# project.net
KiCad netlist of a schematic drawn in EAGLE
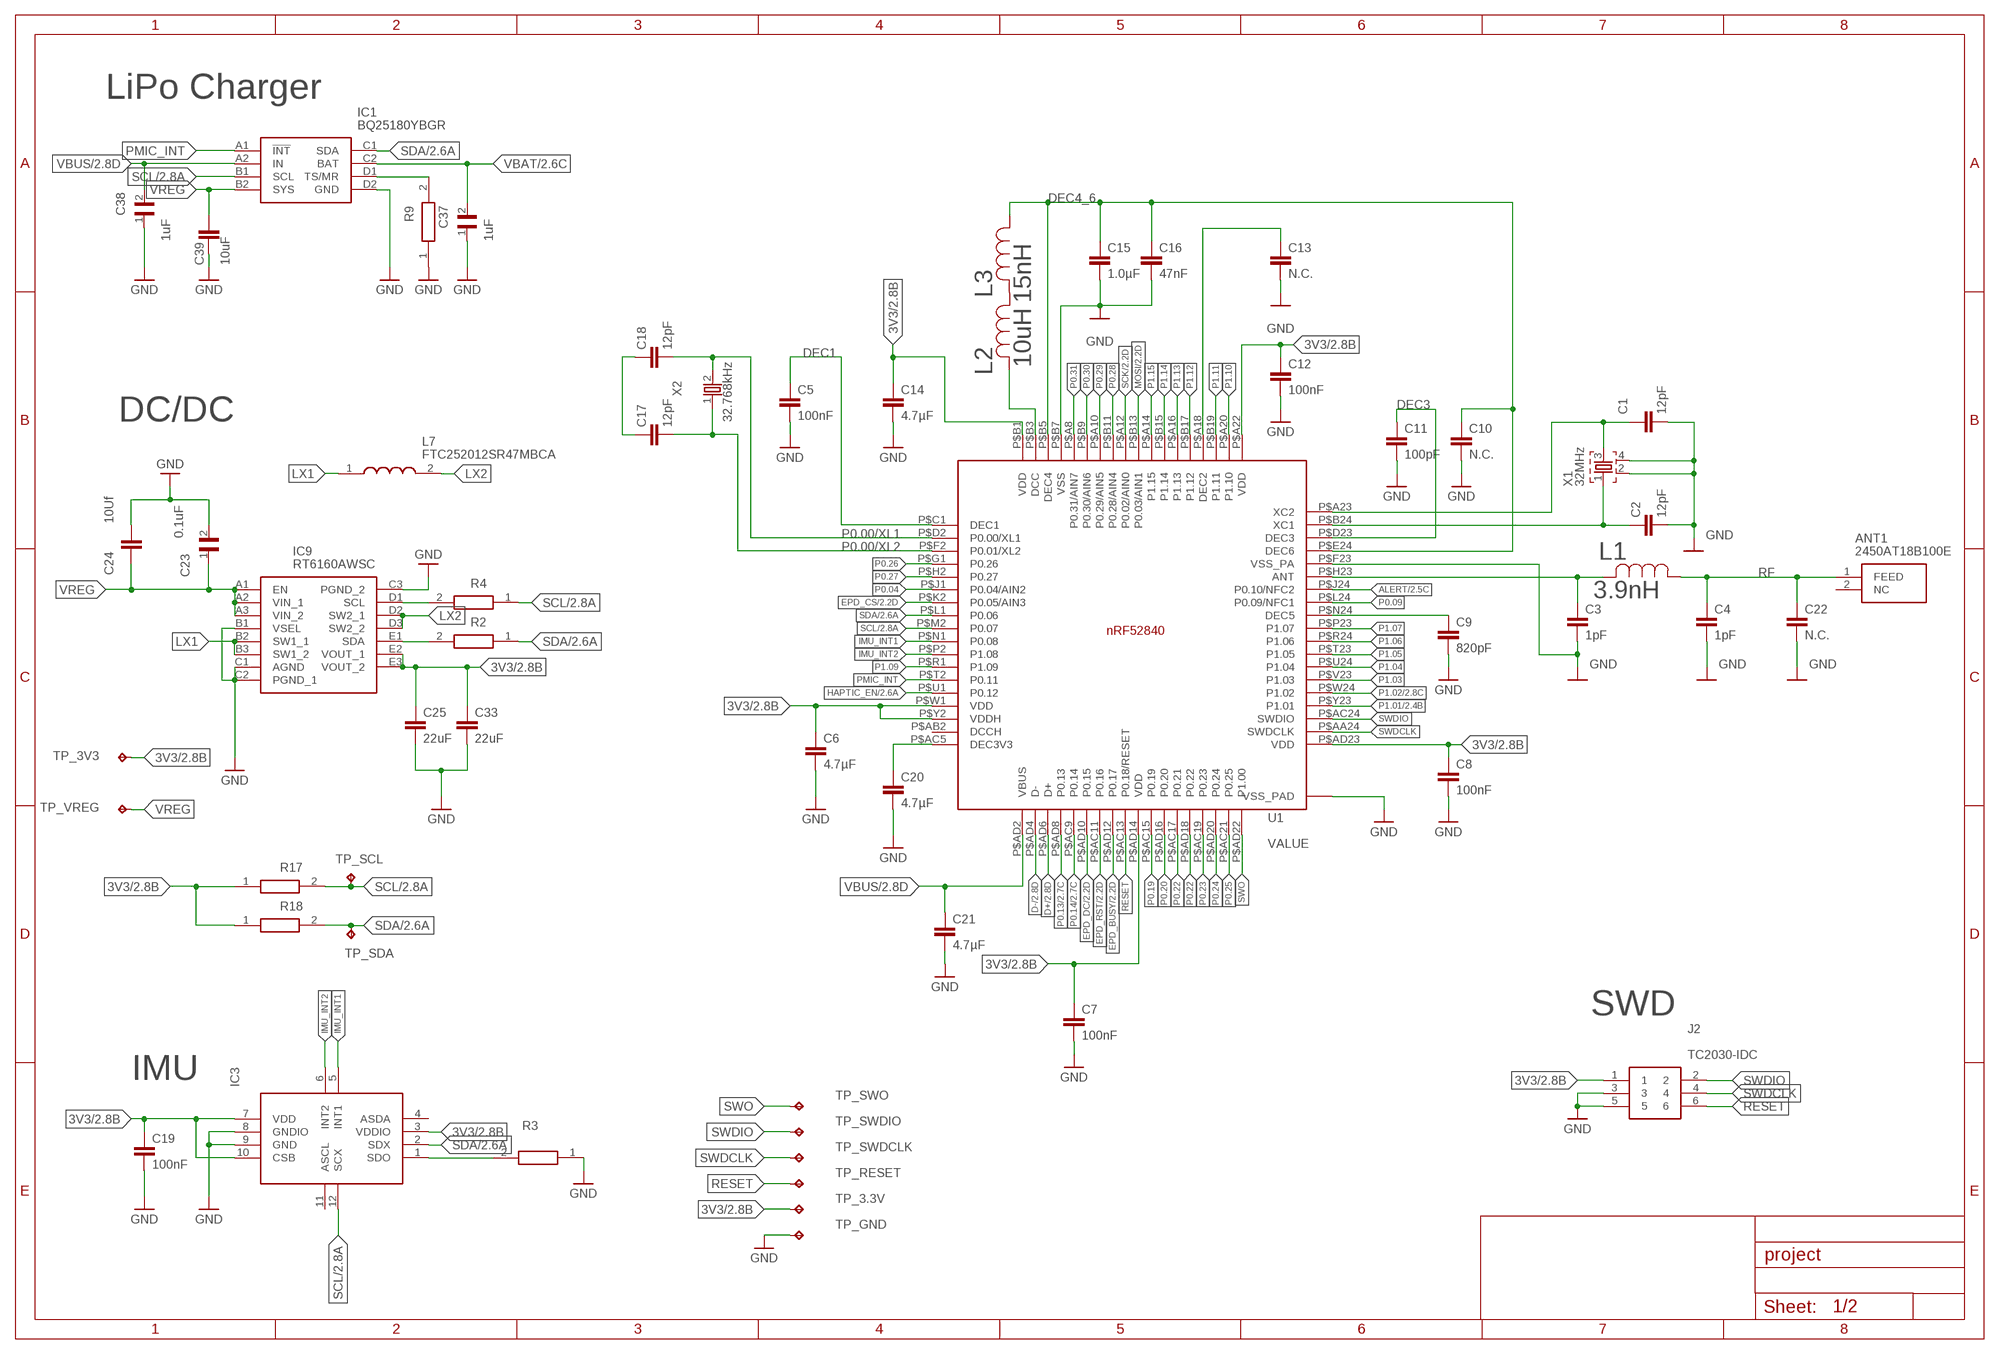
[diagram p0: schematic, sheet 1]
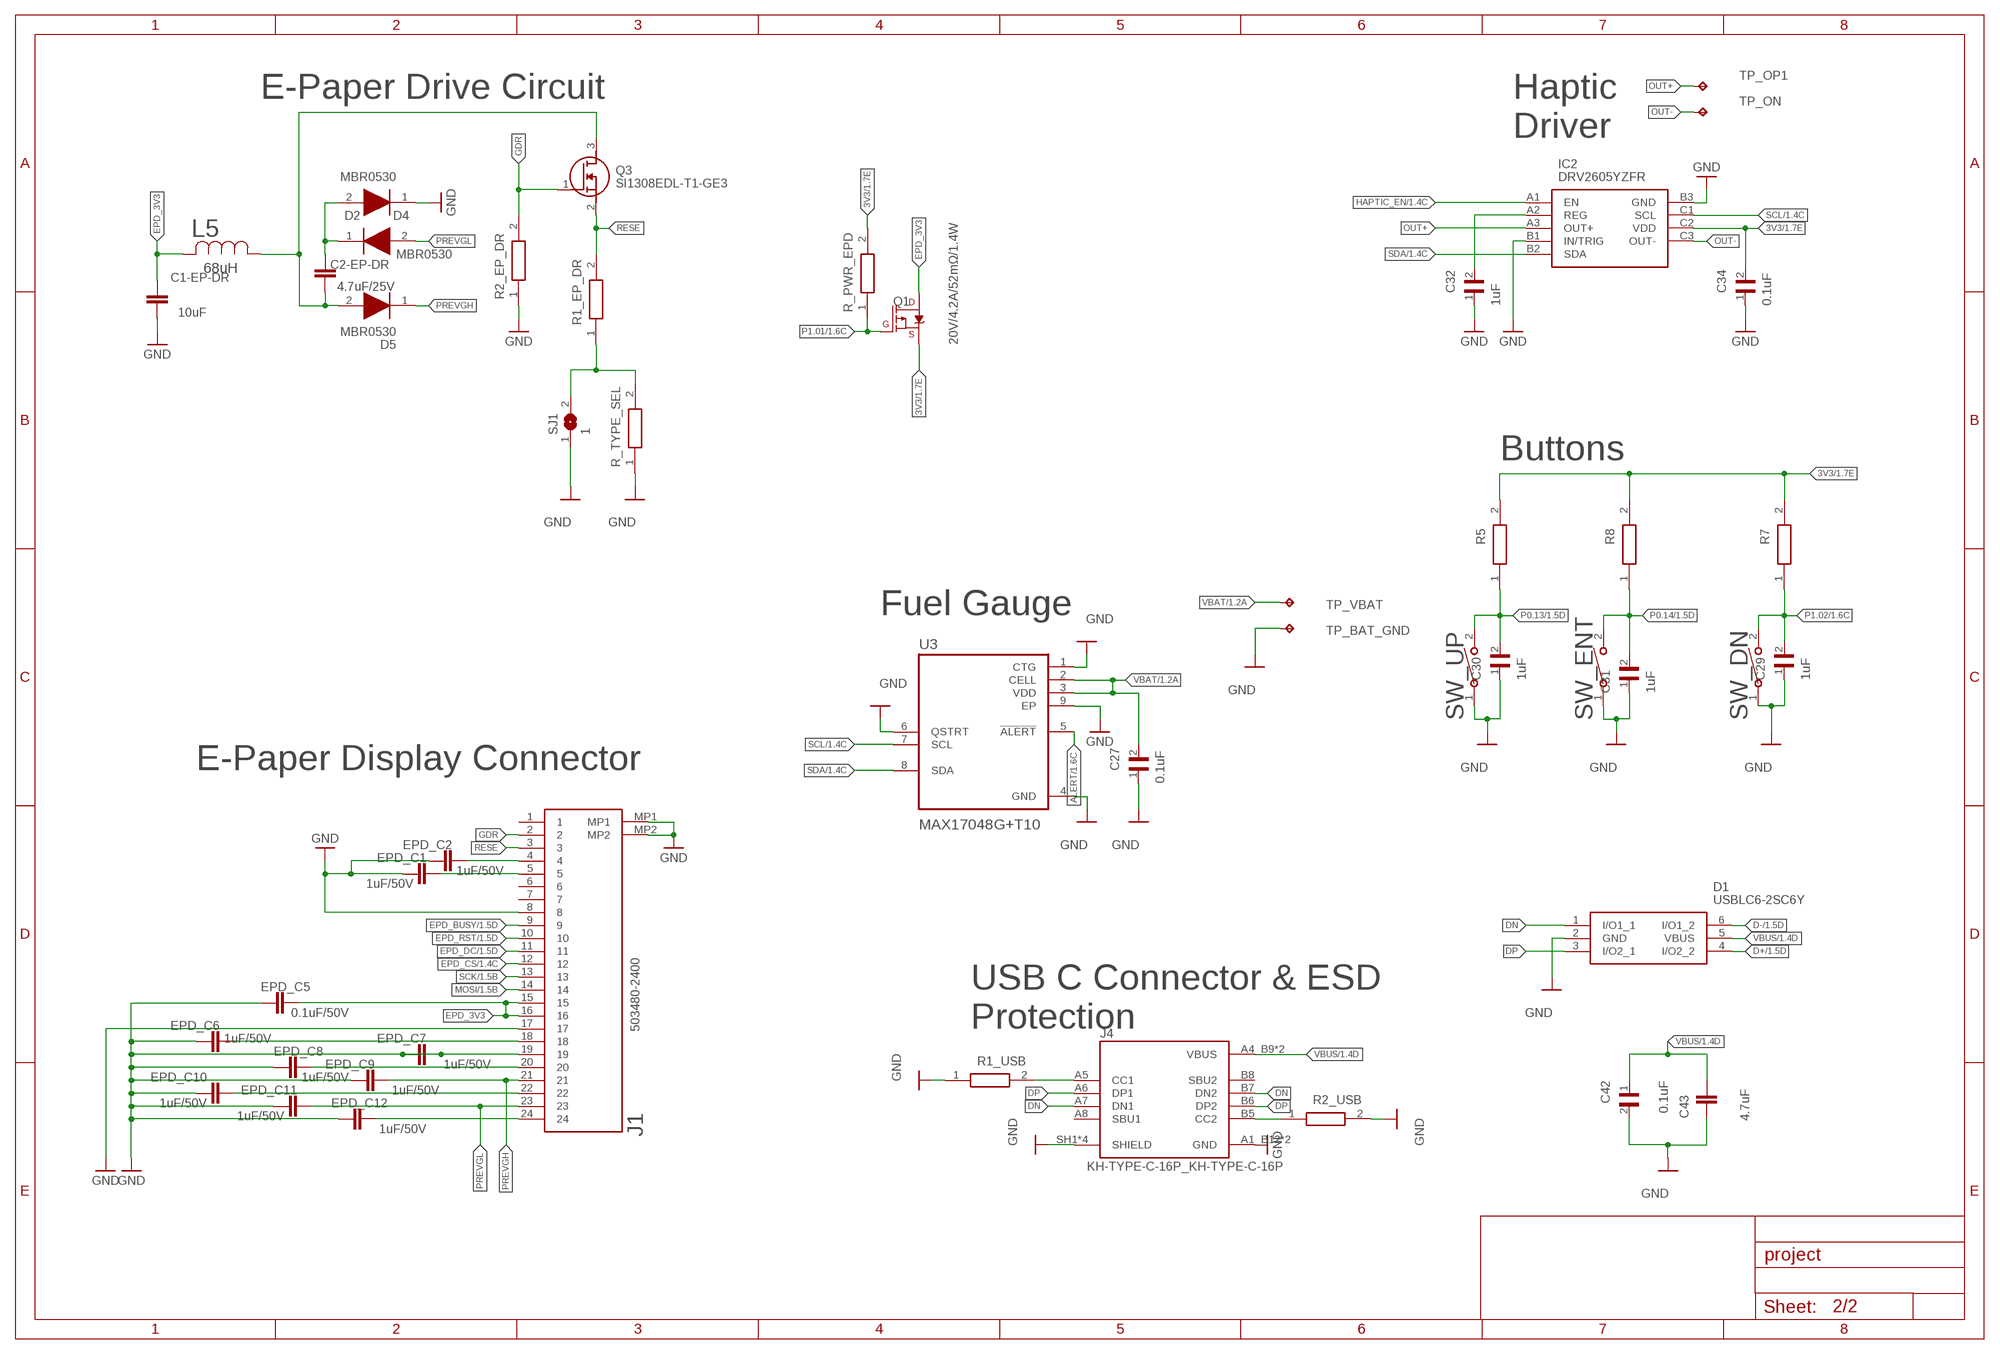
[diagram p1: schematic, sheet 2]

(export (version "E")
  (design (tool "Eeschema 10.0.6"))
  (components
    (comp (ref "C1-EP-DR")
      (value "10uF")
      (footprint "eagle-import:ESP32_C6_LIBRARY_1_ESP32_WROVER_EAGLE-LTSPICE_C0402")
      (libsource (lib "eagle-import") (part "ESP32_C6_LIBRARY_1_ESP32_WROVER_EAGLE-LTSPICE_CC0402"))
    )
    (comp (ref "C2-EP-DR")
      (value "4.7uF/25V")
      (footprint "eagle-import:ESP32_C6_LIBRARY_1_ESP32_WROVER_EAGLE-LTSPICE_C0402")
      (libsource (lib "eagle-import") (part "ESP32_C6_LIBRARY_1_ESP32_WROVER_EAGLE-LTSPICE_CC0402"))
    )
    (comp (ref "C27")
      (value "0.1uF")
      (footprint "eagle-import:GRM011R60J152KE01L_1_0201")
      (libsource (lib "eagle-import") (part "GRM011R60J152KE01L_1_GRM011R60J152KE01L"))
    )
    (comp (ref "C29")
      (value "1uF")
      (footprint "eagle-import:GRM011R60J152KE01L_1_0201")
      (libsource (lib "eagle-import") (part "GRM011R60J152KE01L_1_GRM011R60J152KE01L"))
    )
    (comp (ref "C30")
      (value "1uF")
      (footprint "eagle-import:GRM011R60J152KE01L_1_0201")
      (libsource (lib "eagle-import") (part "GRM011R60J152KE01L_1_GRM011R60J152KE01L"))
    )
    (comp (ref "C31")
      (value "1uF")
      (footprint "eagle-import:GRM011R60J152KE01L_1_0201")
      (libsource (lib "eagle-import") (part "GRM011R60J152KE01L_1_GRM011R60J152KE01L"))
    )
    (comp (ref "C32")
      (value "1uF")
      (footprint "eagle-import:GRM011R60J152KE01L_1_0201")
      (libsource (lib "eagle-import") (part "GRM011R60J152KE01L_1_GRM011R60J152KE01L"))
    )
    (comp (ref "C34")
      (value "0.1uF")
      (footprint "eagle-import:GRM011R60J152KE01L_1_0201")
      (libsource (lib "eagle-import") (part "GRM011R60J152KE01L_1_GRM011R60J152KE01L"))
    )
    (comp (ref "C42")
      (value "0.1uF")
      (footprint "eagle-import:GRM011R60J152KE01L_1_0201")
      (libsource (lib "eagle-import") (part "GRM011R60J152KE01L_1_GRM011R60J152KE01L"))
    )
    (comp (ref "C43")
      (value "4.7uF")
      (footprint "eagle-import:ESP32_C6_LIBRARY_1_ESP32_WROVER_EAGLE-LTSPICE_C0402")
      (libsource (lib "eagle-import") (part "ESP32_C6_LIBRARY_1_ESP32_WROVER_EAGLE-LTSPICE_CC0402"))
    )
    (comp (ref "D1")
      (value "USBLC6-2SC6Y")
      (footprint "eagle-import:ESP32_C6_LIBRARY_3_SOT95P280X145-6N")
      (fields (field (name "MF") "STMicroelectronics"))
      (libsource (lib "eagle-import") (part "ESP32_C6_LIBRARY_3_USBLC6-2SC6Y"))
    )
    (comp (ref "D2")
      (value "MBR0530")
      (footprint "eagle-import:ESP32_C6_LIBRARY_5_SOD3716X135N")
      (fields (field (name "MF") "ON Semiconductor"))
      (libsource (lib "eagle-import") (part "ESP32_C6_LIBRARY_5_MBR0530"))
    )
    (comp (ref "D4")
      (value "MBR0530")
      (footprint "eagle-import:ESP32_C6_LIBRARY_5_SOD3716X135N")
      (fields (field (name "MF") "ON Semiconductor"))
      (libsource (lib "eagle-import") (part "ESP32_C6_LIBRARY_5_MBR0530"))
    )
    (comp (ref "D5")
      (value "MBR0530")
      (footprint "eagle-import:ESP32_C6_LIBRARY_5_SOD3716X135N")
      (fields (field (name "MF") "ON Semiconductor"))
      (libsource (lib "eagle-import") (part "ESP32_C6_LIBRARY_5_MBR0530"))
    )
    (comp (ref "EPD_C1")
      (value "1uF/50V")
      (footprint "eagle-import:ESP32_C6_LIBRARY_1_ESP32_WROVER_EAGLE-LTSPICE_C0402")
      (libsource (lib "eagle-import") (part "ESP32_C6_LIBRARY_1_ESP32_WROVER_EAGLE-LTSPICE_CC0402"))
    )
    (comp (ref "EPD_C2")
      (value "1uF/50V")
      (footprint "eagle-import:ESP32_C6_LIBRARY_1_ESP32_WROVER_EAGLE-LTSPICE_C0402")
      (libsource (lib "eagle-import") (part "ESP32_C6_LIBRARY_1_ESP32_WROVER_EAGLE-LTSPICE_CC0402"))
    )
    (comp (ref "EPD_C5")
      (value "0.1uF/50V")
      (footprint "eagle-import:ESP32_C6_LIBRARY_1_ESP32_WROVER_EAGLE-LTSPICE_C0402")
      (libsource (lib "eagle-import") (part "ESP32_C6_LIBRARY_1_ESP32_WROVER_EAGLE-LTSPICE_CC0402"))
    )
    (comp (ref "EPD_C6")
      (value "1uF/50V")
      (footprint "eagle-import:ESP32_C6_LIBRARY_1_ESP32_WROVER_EAGLE-LTSPICE_C0402")
      (libsource (lib "eagle-import") (part "ESP32_C6_LIBRARY_1_ESP32_WROVER_EAGLE-LTSPICE_CC0402"))
    )
    (comp (ref "EPD_C7")
      (value "1uF/50V")
      (footprint "eagle-import:ESP32_C6_LIBRARY_1_ESP32_WROVER_EAGLE-LTSPICE_C0402")
      (libsource (lib "eagle-import") (part "ESP32_C6_LIBRARY_1_ESP32_WROVER_EAGLE-LTSPICE_CC0402"))
    )
    (comp (ref "EPD_C8")
      (value "1uF/50V")
      (footprint "eagle-import:ESP32_C6_LIBRARY_1_ESP32_WROVER_EAGLE-LTSPICE_C0402")
      (libsource (lib "eagle-import") (part "ESP32_C6_LIBRARY_1_ESP32_WROVER_EAGLE-LTSPICE_CC0402"))
    )
    (comp (ref "EPD_C9")
      (value "1uF/50V")
      (footprint "eagle-import:ESP32_C6_LIBRARY_1_ESP32_WROVER_EAGLE-LTSPICE_C0402")
      (libsource (lib "eagle-import") (part "ESP32_C6_LIBRARY_1_ESP32_WROVER_EAGLE-LTSPICE_CC0402"))
    )
    (comp (ref "EPD_C10")
      (value "1uF/50V")
      (footprint "eagle-import:ESP32_C6_LIBRARY_1_ESP32_WROVER_EAGLE-LTSPICE_C0402")
      (libsource (lib "eagle-import") (part "ESP32_C6_LIBRARY_1_ESP32_WROVER_EAGLE-LTSPICE_CC0402"))
    )
    (comp (ref "EPD_C11")
      (value "1uF/50V")
      (footprint "eagle-import:ESP32_C6_LIBRARY_1_ESP32_WROVER_EAGLE-LTSPICE_C0402")
      (libsource (lib "eagle-import") (part "ESP32_C6_LIBRARY_1_ESP32_WROVER_EAGLE-LTSPICE_CC0402"))
    )
    (comp (ref "EPD_C12")
      (value "1uF/50V")
      (footprint "eagle-import:ESP32_C6_LIBRARY_1_ESP32_WROVER_EAGLE-LTSPICE_C0402")
      (libsource (lib "eagle-import") (part "ESP32_C6_LIBRARY_1_ESP32_WROVER_EAGLE-LTSPICE_CC0402"))
    )
    (comp (ref "IC2")
      (value "DRV2605YZFR")
      (footprint "eagle-import:DRV2605YZFR_BGA9C50P3X3_144X144X62")
      (libsource (lib "eagle-import") (part "DRV2605YZFR_DRV2605YZFR"))
    )
    (comp (ref "J1")
      (value "503480-2400")
      (footprint "eagle-import:503480-2400_5034802400")
      (fields (field (name "MOUSER_PART_NUMBER") "538-503480-2400"))
      (libsource (lib "eagle-import") (part "503480-2400_503480-2400"))
    )
    (comp (ref "J4")
      (value "KH-TYPE-C-16P_KH-TYPE-C-16P")
      (footprint "eagle-import:KH-TYPE-C-16P_KINGHELM_KH-TYPE-C-16P")
      (fields (field (name "MF") "kinghelm") (field (name "MP") "KH-TYPE-C-16P"))
      (libsource (lib "eagle-import") (part "KH-TYPE-C-16P_KH-TYPE-C-16P"))
    )
    (comp (ref "L5")
      (value "68uH")
      (footprint "eagle-import:ESP32_C6_LIBRARY_2_IND_4828-WE-TPC_WRE")
      (fields
        (field (name "MANUFACTURER_PART_NUMBER") "744043680")
        (field (name "COPYRIGHT") "Copyright (C) 2024 Ultra Librarian. All rights reserved.")
      )
      (libsource (lib "eagle-import") (part "ESP32_C6_LIBRARY_2_744043680IND_4828-WE-TPC_WRE"))
    )
    (comp (ref "Q1")
      (value "20V/4.2A/52mΩ/1.4W")
      (footprint "eagle-import:ESP32_C6_LIBRARY_4_ESP32_C6_LIBRARY_4_ESP32_C6_LIBRARY_4_ESP32_C6_LIBRARY_4_ESP32_WROVER_SPARKFUN-DISCRETESEMI_SOT23-3")
      (libsource (lib "eagle-import") (part "ESP32_C6_LIBRARY_4_ESP32_WROVER_SPARKFUN-DISCRETESEMI_MOSFET_PCH-DMG2305UX-7"))
    )
    (comp (ref "Q3")
      (value "SI1308EDL-T1-GE3")
      (footprint "eagle-import:ESP32_C6_LIBRARY_6_SOT65P210X110-3N")
      (fields (field (name "MF") "Vishay Siliconix"))
      (libsource (lib "eagle-import") (part "ESP32_C6_LIBRARY_6_SI1308EDL-T1-GE3"))
    )
    (comp (ref "R1_EP_DR")
      (value "0.47")
      (footprint "eagle-import:ERA-1AEB3401C_0201")
      (libsource (lib "eagle-import") (part "ERA-1AEB3401C_CPF0201D7K68C1"))
    )
    (comp (ref "R1_USB")
      (value "5k1")
      (footprint "eagle-import:ERA-1AEB3401C_0201")
      (libsource (lib "eagle-import") (part "ERA-1AEB3401C_CPF0201D7K68C1"))
    )
    (comp (ref "R2_EP_DR")
      (value "10K")
      (footprint "eagle-import:ERA-1AEB3401C_0201")
      (libsource (lib "eagle-import") (part "ERA-1AEB3401C_CPF0201D7K68C1"))
    )
    (comp (ref "R2_USB")
      (value "5k1")
      (footprint "eagle-import:ERA-1AEB3401C_0201")
      (libsource (lib "eagle-import") (part "ERA-1AEB3401C_CPF0201D7K68C1"))
    )
    (comp (ref "R5")
      (value "10K")
      (footprint "eagle-import:ERA-1AEB3401C_0201")
      (libsource (lib "eagle-import") (part "ERA-1AEB3401C_CPF0201D7K68C1"))
    )
    (comp (ref "R7")
      (value "10K")
      (footprint "eagle-import:ERA-1AEB3401C_0201")
      (libsource (lib "eagle-import") (part "ERA-1AEB3401C_CPF0201D7K68C1"))
    )
    (comp (ref "R8")
      (value "10K")
      (footprint "eagle-import:ERA-1AEB3401C_0201")
      (libsource (lib "eagle-import") (part "ERA-1AEB3401C_CPF0201D7K68C1"))
    )
    (comp (ref "R_PWR_EPD")
      (value "10K")
      (footprint "eagle-import:ERA-1AEB3401C_0201")
      (libsource (lib "eagle-import") (part "ERA-1AEB3401C_CPF0201D7K68C1"))
    )
    (comp (ref "R_TYPE_SEL")
      (value "2.2")
      (footprint "eagle-import:ERA-1AEB3401C_0201")
      (libsource (lib "eagle-import") (part "ERA-1AEB3401C_CPF0201D7K68C1"))
    )
    (comp (ref "SJ1")
      (value "1")
      (footprint "eagle-import:ESP32_C6_LIBRARY_7_JUMPER_SJ")
      (libsource (lib "eagle-import") (part "ESP32_C6_LIBRARY_7_JUMPER_SJ"))
    )
    (comp (ref "SW_DN")
      (value "2025-10-22_07-23-44_LIBRARY_EVP-AKE31ASW_EVP-AKE31A_PAN")
      (footprint "eagle-import:2025-10-22_07-23-44_LIBRARY_SW_EVP-AKE31A_PAN")
      (fields
        (field (name "MANUFACTURER_PART_NUMBER") "EVP-AKE31A")
        (field (name "COPYRIGHT") "Copyright (C) 2025 Ultra Librarian. All rights reserved.")
      )
      (libsource (lib "eagle-import") (part "2025-10-22_07-23-44_LIBRARY_EVP-AKE31ASW_EVP-AKE31A_PAN"))
    )
    (comp (ref "SW_ENT")
      (value "2025-10-22_07-23-44_LIBRARY_EVP-AKE31ASW_EVP-AKE31A_PAN")
      (footprint "eagle-import:2025-10-22_07-23-44_LIBRARY_SW_EVP-AKE31A_PAN")
      (fields
        (field (name "MANUFACTURER_PART_NUMBER") "EVP-AKE31A")
        (field (name "COPYRIGHT") "Copyright (C) 2025 Ultra Librarian. All rights reserved.")
      )
      (libsource (lib "eagle-import") (part "2025-10-22_07-23-44_LIBRARY_EVP-AKE31ASW_EVP-AKE31A_PAN"))
    )
    (comp (ref "SW_UP")
      (value "SW_UP")
      (footprint "eagle-import:2025-10-22_07-23-44_LIBRARY_SW_EVP-AKE31A_PAN")
      (fields
        (field (name "MANUFACTURER_PART_NUMBER") "EVP-AKE31A")
        (field (name "COPYRIGHT") "Copyright (C) 2025 Ultra Librarian. All rights reserved.")
      )
      (libsource (lib "eagle-import") (part "2025-10-22_07-23-44_LIBRARY_EVP-AKE31ASW_EVP-AKE31A_PAN"))
    )
    (comp (ref "TP_BAT_GND")
      (value "HECTOR_WATCH_1_TPTP20R")
      (footprint "eagle-import:HECTOR_WATCH_1_TP20R")
      (libsource (lib "eagle-import") (part "HECTOR_WATCH_1_TPTP20R"))
    )
    (comp (ref "TP_ON")
      (value "HECTOR_WATCH_1_TPTP20R")
      (footprint "eagle-import:HECTOR_WATCH_1_TP20R")
      (libsource (lib "eagle-import") (part "HECTOR_WATCH_1_TPTP20R"))
    )
    (comp (ref "TP_OP1")
      (value "HECTOR_WATCH_1_TPTP20R")
      (footprint "eagle-import:HECTOR_WATCH_1_TP20R")
      (libsource (lib "eagle-import") (part "HECTOR_WATCH_1_TPTP20R"))
    )
    (comp (ref "TP_VBAT")
      (value "3V3")
      (footprint "eagle-import:HECTOR_WATCH_1_TP20R")
      (libsource (lib "eagle-import") (part "HECTOR_WATCH_1_TPTP20R"))
    )
    (comp (ref "U3")
      (value "MAX17048G+T10")
      (footprint "eagle-import:ESP32_C6_LIBRARY_SON50P200X200X80-9N")
      (fields (field (name "MF") "Analog Devices"))
      (libsource (lib "eagle-import") (part "ESP32_C6_LIBRARY_MAX17048G+T10"))
    )
    (comp (ref "ANT1")
      (value "2450AT18B100E")
      (footprint "eagle-import:2450AT18B100E_ANTC3216X140N")
      (fields (field (name "MOUSER_PART_NUMBER") "609-2450AT18B100E"))
      (libsource (lib "eagle-import") (part "2450AT18B100E_2450AT18B100E"))
    )
    (comp (ref "C1")
      (value "12pF")
      (footprint "eagle-import:PERFECT_0402_0402")
      (libsource (lib "eagle-import") (part "PERFECT_0402_CAP_0402"))
    )
    (comp (ref "C2")
      (value "12pF")
      (footprint "eagle-import:PERFECT_0402_0402")
      (libsource (lib "eagle-import") (part "PERFECT_0402_CAP_0402"))
    )
    (comp (ref "C3")
      (value "1pF")
      (footprint "eagle-import:PERFECT_0402_0402")
      (libsource (lib "eagle-import") (part "PERFECT_0402_CAP_0402"))
    )
    (comp (ref "C4")
      (value "1pF")
      (footprint "eagle-import:PERFECT_0402_0402")
      (libsource (lib "eagle-import") (part "PERFECT_0402_CAP_0402"))
    )
    (comp (ref "C5")
      (value "100nF")
      (footprint "eagle-import:PERFECT_0402_0402")
      (libsource (lib "eagle-import") (part "PERFECT_0402_CAP_0402"))
    )
    (comp (ref "C6")
      (value "4.7µF")
      (footprint "eagle-import:PERFECT_0402_0402")
      (libsource (lib "eagle-import") (part "PERFECT_0402_CAP_0402"))
    )
    (comp (ref "C7")
      (value "100nF")
      (footprint "eagle-import:PERFECT_0402_0402")
      (libsource (lib "eagle-import") (part "PERFECT_0402_CAP_0402"))
    )
    (comp (ref "C8")
      (value "100nF")
      (footprint "eagle-import:PERFECT_0402_0402")
      (libsource (lib "eagle-import") (part "PERFECT_0402_CAP_0402"))
    )
    (comp (ref "C9")
      (value "820pF")
      (footprint "eagle-import:PERFECT_0402_0402")
      (libsource (lib "eagle-import") (part "PERFECT_0402_CAP_0402"))
    )
    (comp (ref "C10")
      (value "N.C.")
      (footprint "eagle-import:PERFECT_0402_0402")
      (libsource (lib "eagle-import") (part "PERFECT_0402_CAP_0402"))
    )
    (comp (ref "C11")
      (value "100pF")
      (footprint "eagle-import:PERFECT_0402_0402")
      (libsource (lib "eagle-import") (part "PERFECT_0402_CAP_0402"))
    )
    (comp (ref "C12")
      (value "100nF")
      (footprint "eagle-import:PERFECT_0402_0402")
      (libsource (lib "eagle-import") (part "PERFECT_0402_CAP_0402"))
    )
    (comp (ref "C13")
      (value "N.C.")
      (footprint "eagle-import:PERFECT_0402_0402")
      (libsource (lib "eagle-import") (part "PERFECT_0402_CAP_0402"))
    )
    (comp (ref "C14")
      (value "4.7µF")
      (footprint "eagle-import:PERFECT_0402_0402")
      (libsource (lib "eagle-import") (part "PERFECT_0402_CAP_0402"))
    )
    (comp (ref "C15")
      (value "1.0µF")
      (footprint "eagle-import:PERFECT_0402_0402")
      (libsource (lib "eagle-import") (part "PERFECT_0402_CAP_0402"))
    )
    (comp (ref "C16")
      (value "47nF")
      (footprint "eagle-import:PERFECT_0402_0402")
      (libsource (lib "eagle-import") (part "PERFECT_0402_CAP_0402"))
    )
    (comp (ref "C17")
      (value "12pF")
      (footprint "eagle-import:PERFECT_0402_0402")
      (libsource (lib "eagle-import") (part "PERFECT_0402_CAP_0402"))
    )
    (comp (ref "C18")
      (value "12pF")
      (footprint "eagle-import:PERFECT_0402_0402")
      (libsource (lib "eagle-import") (part "PERFECT_0402_CAP_0402"))
    )
    (comp (ref "C19")
      (value "100nF")
      (footprint "eagle-import:PERFECT_0402_0402")
      (libsource (lib "eagle-import") (part "PERFECT_0402_CAP_0402"))
    )
    (comp (ref "C20")
      (value "4.7µF")
      (footprint "eagle-import:PERFECT_0402_0402")
      (libsource (lib "eagle-import") (part "PERFECT_0402_CAP_0402"))
    )
    (comp (ref "C21")
      (value "4.7µF")
      (footprint "eagle-import:PERFECT_0402_0402")
      (libsource (lib "eagle-import") (part "PERFECT_0402_CAP_0402"))
    )
    (comp (ref "C22")
      (value "N.C.")
      (footprint "eagle-import:PERFECT_0402_0402")
      (libsource (lib "eagle-import") (part "PERFECT_0402_CAP_0402"))
    )
    (comp (ref "C23")
      (value "0.1uF")
      (footprint "eagle-import:GRM011R60J152KE01L_1_0201")
      (libsource (lib "eagle-import") (part "GRM011R60J152KE01L_1_GRM011R60J152KE01L"))
    )
    (comp (ref "C24")
      (value "10Uf")
      (footprint "eagle-import:PERFECT_0402_0402")
      (libsource (lib "eagle-import") (part "PERFECT_0402_CAP_0402"))
    )
    (comp (ref "C25")
      (value "22uF")
      (footprint "eagle-import:PERFECT_0402_0402")
      (libsource (lib "eagle-import") (part "PERFECT_0402_CAP_0402"))
    )
    (comp (ref "C33")
      (value "22uF")
      (footprint "eagle-import:PERFECT_0402_0402")
      (libsource (lib "eagle-import") (part "PERFECT_0402_CAP_0402"))
    )
    (comp (ref "C37")
      (value "1uF")
      (footprint "eagle-import:GRM011R60J152KE01L_1_0201")
      (libsource (lib "eagle-import") (part "GRM011R60J152KE01L_1_GRM011R60J152KE01L"))
    )
    (comp (ref "C38")
      (value "1uF")
      (footprint "eagle-import:GRM011R60J152KE01L_1_0201")
      (libsource (lib "eagle-import") (part "GRM011R60J152KE01L_1_GRM011R60J152KE01L"))
    )
    (comp (ref "C39")
      (value "10uF")
      (footprint "eagle-import:PERFECT_0402_0402")
      (libsource (lib "eagle-import") (part "PERFECT_0402_CAP_0402"))
    )
    (comp (ref "IC1")
      (value "BQ25180YBGR")
      (footprint "eagle-import:BQ25180YBGR_BGA8C40P2X4_100X155X50")
      (fields (field (name "MOUSER_PART_NUMBER") "595-BQ25180YBGR"))
      (libsource (lib "eagle-import") (part "BQ25180YBGR_BQ25180YBGR"))
    )
    (comp (ref "IC3")
      (value "BMA421")
      (footprint "eagle-import:BMA423_BMA423")
      (fields
        (field (name "MANUFACTURER_PART_NUMBER") "BMA423")
        (field (name "MOUSER_PART_NUMBER") "262-BMA423")
      )
      (libsource (lib "eagle-import") (part "BMA423_BMA423"))
    )
    (comp (ref "IC9")
      (value "RT6160AWSC")
      (footprint "eagle-import:RT6160AWSC_BGA15C40P3X5_140X230X60")
      (fields (field (name "MOUSER_PART_NUMBER") "835-RT6160AWSC"))
      (libsource (lib "eagle-import") (part "RT6160AWSC_RT6160AWSC"))
    )
    (comp (ref "J2")
      (value "TC2030-IDC")
      (footprint "eagle-import:TC2030-IDC_TC2030IDC")
      (libsource (lib "eagle-import") (part "TC2030-IDC_TC2030-IDC"))
    )
    (comp (ref "L1")
      (value "3.9nH")
      (footprint "eagle-import:ESP32_C6_LIBRARY_2_IND_4828-WE-TPC_WRE")
      (fields
        (field (name "MANUFACTURER_PART_NUMBER") "744043680")
        (field (name "COPYRIGHT") "Copyright (C) 2024 Ultra Librarian. All rights reserved.")
      )
      (libsource (lib "eagle-import") (part "ESP32_C6_LIBRARY_2_744043680IND_4828-WE-TPC_WRE"))
    )
    (comp (ref "L2")
      (value "10uH")
      (footprint "eagle-import:ESP32_C6_LIBRARY_2_IND_4828-WE-TPC_WRE")
      (fields
        (field (name "MANUFACTURER_PART_NUMBER") "744043680")
        (field (name "COPYRIGHT") "Copyright (C) 2024 Ultra Librarian. All rights reserved.")
      )
      (libsource (lib "eagle-import") (part "ESP32_C6_LIBRARY_2_744043680IND_4828-WE-TPC_WRE"))
    )
    (comp (ref "L3")
      (value "15nH")
      (footprint "eagle-import:ESP32_C6_LIBRARY_2_IND_4828-WE-TPC_WRE")
      (fields
        (field (name "MANUFACTURER_PART_NUMBER") "744043680")
        (field (name "COPYRIGHT") "Copyright (C) 2024 Ultra Librarian. All rights reserved.")
      )
      (libsource (lib "eagle-import") (part "ESP32_C6_LIBRARY_2_744043680IND_4828-WE-TPC_WRE"))
    )
    (comp (ref "L7")
      (value "FTC252012SR47MBCA")
      (footprint "eagle-import:MLP2016SR47MT0S1_INDC2016X100N")
      (libsource (lib "eagle-import") (part "MLP2016SR47MT0S1_FTC252012SR47MBCA"))
    )
    (comp (ref "R2")
      (value "0")
      (footprint "eagle-import:ERA-1AEB3401C_0201")
      (libsource (lib "eagle-import") (part "ERA-1AEB3401C_CPF0201D7K68C1"))
    )
    (comp (ref "R3")
      (value "ERA-1AEB3401C_CPF0201D7K68C1")
      (footprint "eagle-import:ERA-1AEB3401C_0201")
      (libsource (lib "eagle-import") (part "ERA-1AEB3401C_CPF0201D7K68C1"))
    )
    (comp (ref "R4")
      (value "0")
      (footprint "eagle-import:ERA-1AEB3401C_0201")
      (libsource (lib "eagle-import") (part "ERA-1AEB3401C_CPF0201D7K68C1"))
    )
    (comp (ref "R9")
      (value "10K")
      (footprint "eagle-import:ERA-1AEB3401C_0201")
      (libsource (lib "eagle-import") (part "ERA-1AEB3401C_CPF0201D7K68C1"))
    )
    (comp (ref "R17")
      (value "3K3")
      (footprint "eagle-import:ERA-1AEB3401C_0201")
      (libsource (lib "eagle-import") (part "ERA-1AEB3401C_CPF0201D7K68C1"))
    )
    (comp (ref "R18")
      (value "3K3")
      (footprint "eagle-import:ERA-1AEB3401C_0201")
      (libsource (lib "eagle-import") (part "ERA-1AEB3401C_CPF0201D7K68C1"))
    )
    (comp (ref "TP_3.3V")
      (value "HECTOR_WATCH_1_TPTP20R")
      (footprint "eagle-import:HECTOR_WATCH_1_TP20R")
      (libsource (lib "eagle-import") (part "HECTOR_WATCH_1_TPTP20R"))
    )
    (comp (ref "TP_3V3")
      (value "HECTOR_WATCH_1_TPTP20R")
      (footprint "eagle-import:HECTOR_WATCH_1_TP20R")
      (libsource (lib "eagle-import") (part "HECTOR_WATCH_1_TPTP20R"))
    )
    (comp (ref "TP_GND")
      (value "HECTOR_WATCH_1_TPTP20R")
      (footprint "eagle-import:HECTOR_WATCH_1_TP20R")
      (libsource (lib "eagle-import") (part "HECTOR_WATCH_1_TPTP20R"))
    )
    (comp (ref "TP_RESET")
      (value "HECTOR_WATCH_1_TPTP20R")
      (footprint "eagle-import:HECTOR_WATCH_1_TP20R")
      (libsource (lib "eagle-import") (part "HECTOR_WATCH_1_TPTP20R"))
    )
    (comp (ref "TP_SCL")
      (value "HECTOR_WATCH_1_TPTP20R")
      (footprint "eagle-import:HECTOR_WATCH_1_TP20R")
      (libsource (lib "eagle-import") (part "HECTOR_WATCH_1_TPTP20R"))
    )
    (comp (ref "TP_SDA")
      (value "HECTOR_WATCH_1_TPTP20R")
      (footprint "eagle-import:HECTOR_WATCH_1_TP20R")
      (libsource (lib "eagle-import") (part "HECTOR_WATCH_1_TPTP20R"))
    )
    (comp (ref "TP_SWDCLK")
      (value "HECTOR_WATCH_1_TPTP20R")
      (footprint "eagle-import:HECTOR_WATCH_1_TP20R")
      (libsource (lib "eagle-import") (part "HECTOR_WATCH_1_TPTP20R"))
    )
    (comp (ref "TP_SWDIO")
      (value "HECTOR_WATCH_1_TPTP20R")
      (footprint "eagle-import:HECTOR_WATCH_1_TP20R")
      (libsource (lib "eagle-import") (part "HECTOR_WATCH_1_TPTP20R"))
    )
    (comp (ref "TP_SWO")
      (value "HECTOR_WATCH_1_TPTP20R")
      (footprint "eagle-import:HECTOR_WATCH_1_TP20R")
      (libsource (lib "eagle-import") (part "HECTOR_WATCH_1_TPTP20R"))
    )
    (comp (ref "TP_VREG")
      (value "HECTOR_WATCH_1_TPTP20R")
      (footprint "eagle-import:HECTOR_WATCH_1_TP20R")
      (libsource (lib "eagle-import") (part "HECTOR_WATCH_1_TPTP20R"))
    )
    (comp (ref "U1")
      (value "NRF52840_QF")
      (footprint "eagle-import:NORDIC_NRF_4_AQFN50P700X700X85_HS-74N")
      (libsource (lib "eagle-import") (part "NORDIC_NRF_4_NRF52840_QF"))
    )
    (comp (ref "X1")
      (value "32MHz")
      (footprint "eagle-import:NORDIC_NRF_BT-XTAL_2016_N")
      (libsource (lib "eagle-import") (part "NORDIC_NRF_XTAL_32MHZ"))
    )
    (comp (ref "X2")
      (value "32.768kHz")
      (footprint "eagle-import:NORDIC_NRF_1_XTAL_3215_N")
      (libsource (lib "eagle-import") (part "NORDIC_NRF_1_XTAL_32KHZ"))
    )
  )
  (nets
    (net (code "1") (name "3V3") (class "Default")
      (node (ref "C12") (pin "1") (pinfunction "1_1") (pintype "passive"))
      (node (ref "C14") (pin "1") (pinfunction "1_1") (pintype "passive"))
      (node (ref "C19") (pin "1") (pinfunction "1_1") (pintype "passive"))
      (node (ref "C25") (pin "1") (pinfunction "1_1") (pintype "passive"))
      (node (ref "C33") (pin "1") (pinfunction "1_1") (pintype "passive"))
      (node (ref "C34") (pin "2") (pinfunction "2_2") (pintype "passive"))
      (node (ref "C6") (pin "1") (pinfunction "1_1") (pintype "passive"))
      (node (ref "C7") (pin "1") (pinfunction "1_1") (pintype "passive"))
      (node (ref "C8") (pin "1") (pinfunction "1_1") (pintype "passive"))
      (node (ref "IC2") (pin "C2") (pinfunction "VDD_C2") (pintype "bidirectional"))
      (node (ref "IC3") (pin "10") (pinfunction "CSB_10") (pintype "bidirectional"))
      (node (ref "IC3") (pin "3") (pinfunction "VDDIO_3") (pintype "bidirectional"))
      (node (ref "IC3") (pin "7") (pinfunction "VDD_7") (pintype "bidirectional"))
      (node (ref "IC9") (pin "E2") (pinfunction "VOUT_1_E2") (pintype "bidirectional"))
      (node (ref "IC9") (pin "E3") (pinfunction "VOUT_2_E3") (pintype "bidirectional"))
      (node (ref "J2") (pin "1") (pinfunction "1_1") (pintype "bidirectional"))
      (node (ref "Q1") (pin "2") (pinfunction "S_2") (pintype "bidirectional"))
      (node (ref "R17") (pin "1") (pinfunction "1_1") (pintype "bidirectional"))
      (node (ref "R18") (pin "1") (pinfunction "1_1") (pintype "bidirectional"))
      (node (ref "R5") (pin "2") (pinfunction "2_2") (pintype "bidirectional"))
      (node (ref "R7") (pin "2") (pinfunction "2_2") (pintype "bidirectional"))
      (node (ref "R8") (pin "2") (pinfunction "2_2") (pintype "bidirectional"))
      (node (ref "R_PWR_EPD") (pin "2") (pinfunction "2_2") (pintype "bidirectional"))
      (node (ref "TP_3.3V") (pin "TP") (pinfunction "TP_TP") (pintype "input"))
      (node (ref "TP_3V3") (pin "TP") (pinfunction "TP_TP") (pintype "input"))
      (node (ref "U1") (pin "P$A22") (pinfunction "VDD_P$A22") (pintype "power_in"))
      (node (ref "U1") (pin "P$AD14") (pinfunction "VDD_P$AD14") (pintype "power_in"))
      (node (ref "U1") (pin "P$AD23") (pinfunction "VDD_P$AD23") (pintype "power_in"))
      (node (ref "U1") (pin "P$B1") (pinfunction "VDD_P$B1") (pintype "power_in"))
      (node (ref "U1") (pin "P$W1") (pinfunction "VDD_P$W1") (pintype "power_in"))
      (node (ref "U1") (pin "P$Y2") (pinfunction "VDDH_P$Y2") (pintype "power_in"))
    )
    (net (code "2") (name "ALERT") (class "Default")
      (node (ref "U1") (pin "P$J24") (pinfunction "P0.10/NFC2_P$J24") (pintype "bidirectional"))
      (node (ref "U3") (pin "5") (pinfunction "~{ALERT}_5") (pintype "output"))
    )
    (net (code "3") (name "D+") (class "Default")
      (node (ref "D1") (pin "4") (pinfunction "I/O2_2_4") (pintype "bidirectional"))
      (node (ref "U1") (pin "P$AD6") (pinfunction "D+_P$AD6") (pintype "bidirectional"))
    )
    (net (code "4") (name "D-") (class "Default")
      (node (ref "D1") (pin "6") (pinfunction "I/O1_2_6") (pintype "bidirectional"))
      (node (ref "U1") (pin "P$AD4") (pinfunction "D-_P$AD4") (pintype "bidirectional"))
    )
    (net (code "5") (name "DEC1") (class "Default")
      (node (ref "C5") (pin "1") (pinfunction "1_1") (pintype "passive"))
      (node (ref "U1") (pin "P$C1") (pinfunction "DEC1_P$C1") (pintype "power_in"))
    )
    (net (code "6") (name "DEC3") (class "Default")
      (node (ref "C11") (pin "1") (pinfunction "1_1") (pintype "passive"))
      (node (ref "U1") (pin "P$D23") (pinfunction "DEC3_P$D23") (pintype "bidirectional"))
    )
    (net (code "7") (name "DEC4_6") (class "Default")
      (node (ref "C10") (pin "1") (pinfunction "1_1") (pintype "passive"))
      (node (ref "C15") (pin "1") (pinfunction "1_1") (pintype "passive"))
      (node (ref "C16") (pin "1") (pinfunction "1_1") (pintype "passive"))
      (node (ref "L3") (pin "1") (pinfunction "1_1") (pintype "passive"))
      (node (ref "U1") (pin "P$B5") (pinfunction "DEC4_P$B5") (pintype "power_in"))
      (node (ref "U1") (pin "P$E24") (pinfunction "DEC6_P$E24") (pintype "bidirectional"))
    )
    (net (code "8") (name "DN") (class "Default")
      (node (ref "D1") (pin "1") (pinfunction "I/O1_1_1") (pintype "bidirectional"))
      (node (ref "J4") (pin "A7") (pinfunction "DN1_A7") (pintype "bidirectional"))
      (node (ref "J4") (pin "B7") (pinfunction "DN2_B7") (pintype "bidirectional"))
    )
    (net (code "9") (name "DP") (class "Default")
      (node (ref "D1") (pin "3") (pinfunction "I/O2_1_3") (pintype "bidirectional"))
      (node (ref "J4") (pin "A6") (pinfunction "DP1_A6") (pintype "bidirectional"))
      (node (ref "J4") (pin "B6") (pinfunction "DP2_B6") (pintype "bidirectional"))
    )
    (net (code "10") (name "EPD_3V3") (class "Default")
      (node (ref "C1-EP-DR") (pin "2") (pinfunction "2_2") (pintype "passive"))
      (node (ref "EPD_C5") (pin "2") (pinfunction "2_2") (pintype "passive"))
      (node (ref "J1") (pin "15") (pinfunction "15_15") (pintype "bidirectional"))
      (node (ref "J1") (pin "16") (pinfunction "16_16") (pintype "bidirectional"))
      (node (ref "L5") (pin "2") (pinfunction "2_2") (pintype "passive"))
      (node (ref "Q1") (pin "3") (pinfunction "D_3") (pintype "bidirectional"))
    )
    (net (code "11") (name "EPD_BUSY") (class "Default")
      (node (ref "J1") (pin "9") (pinfunction "9_9") (pintype "bidirectional"))
      (node (ref "U1") (pin "P$AD12") (pinfunction "P0.17_P$AD12") (pintype "bidirectional"))
    )
    (net (code "12") (name "EPD_CS") (class "Default")
      (node (ref "J1") (pin "12") (pinfunction "12_12") (pintype "bidirectional"))
      (node (ref "U1") (pin "P$K2") (pinfunction "P0.05/AIN3_P$K2") (pintype "bidirectional"))
    )
    (net (code "13") (name "EPD_DC") (class "Default")
      (node (ref "J1") (pin "11") (pinfunction "11_11") (pintype "bidirectional"))
      (node (ref "U1") (pin "P$AD10") (pinfunction "P0.15_P$AD10") (pintype "bidirectional"))
    )
    (net (code "14") (name "EPD_RST") (class "Default")
      (node (ref "J1") (pin "10") (pinfunction "10_10") (pintype "bidirectional"))
      (node (ref "U1") (pin "P$AC11") (pinfunction "P0.16_P$AC11") (pintype "bidirectional"))
    )
    (net (code "15") (name "GDR") (class "Default")
      (node (ref "J1") (pin "2") (pinfunction "2_2") (pintype "bidirectional"))
      (node (ref "Q3") (pin "1") (pinfunction "G_1") (pintype "bidirectional"))
      (node (ref "R2_EP_DR") (pin "2") (pinfunction "2_2") (pintype "bidirectional"))
    )
    (net (code "16") (name "GND") (class "Default")
      (node (ref "C1") (pin "2") (pinfunction "2_2") (pintype "passive"))
      (node (ref "C1-EP-DR") (pin "1") (pinfunction "1_1") (pintype "passive"))
      (node (ref "C10") (pin "2") (pinfunction "2_2") (pintype "passive"))
      (node (ref "C11") (pin "2") (pinfunction "2_2") (pintype "passive"))
      (node (ref "C12") (pin "2") (pinfunction "2_2") (pintype "passive"))
      (node (ref "C13") (pin "2") (pinfunction "2_2") (pintype "passive"))
      (node (ref "C14") (pin "2") (pinfunction "2_2") (pintype "passive"))
      (node (ref "C15") (pin "2") (pinfunction "2_2") (pintype "passive"))
      (node (ref "C16") (pin "2") (pinfunction "2_2") (pintype "passive"))
      (node (ref "C19") (pin "2") (pinfunction "2_2") (pintype "passive"))
      (node (ref "C2") (pin "2") (pinfunction "2_2") (pintype "passive"))
      (node (ref "C20") (pin "2") (pinfunction "2_2") (pintype "passive"))
      (node (ref "C21") (pin "2") (pinfunction "2_2") (pintype "passive"))
      (node (ref "C22") (pin "2") (pinfunction "2_2") (pintype "passive"))
      (node (ref "C23") (pin "2") (pinfunction "2_2") (pintype "passive"))
      (node (ref "C24") (pin "1") (pinfunction "1_1") (pintype "passive"))
      (node (ref "C25") (pin "2") (pinfunction "2_2") (pintype "passive"))
      (node (ref "C27") (pin "1") (pinfunction "1_1") (pintype "passive"))
      (node (ref "C29") (pin "1") (pinfunction "1_1") (pintype "passive"))
      (node (ref "C3") (pin "2") (pinfunction "2_2") (pintype "passive"))
      (node (ref "C30") (pin "1") (pinfunction "1_1") (pintype "passive"))
      (node (ref "C31") (pin "1") (pinfunction "1_1") (pintype "passive"))
      (node (ref "C32") (pin "1") (pinfunction "1_1") (pintype "passive"))
      (node (ref "C33") (pin "2") (pinfunction "2_2") (pintype "passive"))
      (node (ref "C34") (pin "1") (pinfunction "1_1") (pintype "passive"))
      (node (ref "C37") (pin "1") (pinfunction "1_1") (pintype "passive"))
      (node (ref "C38") (pin "1") (pinfunction "1_1") (pintype "passive"))
      (node (ref "C39") (pin "2") (pinfunction "2_2") (pintype "passive"))
      (node (ref "C4") (pin "2") (pinfunction "2_2") (pintype "passive"))
      (node (ref "C42") (pin "2") (pinfunction "2_2") (pintype "passive"))
      (node (ref "C43") (pin "1") (pinfunction "1_1") (pintype "passive"))
      (node (ref "C5") (pin "2") (pinfunction "2_2") (pintype "passive"))
      (node (ref "C6") (pin "2") (pinfunction "2_2") (pintype "passive"))
      (node (ref "C7") (pin "2") (pinfunction "2_2") (pintype "passive"))
      (node (ref "C8") (pin "2") (pinfunction "2_2") (pintype "passive"))
      (node (ref "C9") (pin "2") (pinfunction "2_2") (pintype "passive"))
      (node (ref "D1") (pin "2") (pinfunction "GND_2") (pintype "bidirectional"))
      (node (ref "D4") (pin "1") (pinfunction "K_1") (pintype "bidirectional"))
      (node (ref "EPD_C1") (pin "1") (pinfunction "1_1") (pintype "passive"))
      (node (ref "EPD_C10") (pin "1") (pinfunction "1_1") (pintype "passive"))
      (node (ref "EPD_C11") (pin "1") (pinfunction "1_1") (pintype "passive"))
      (node (ref "EPD_C12") (pin "1") (pinfunction "1_1") (pintype "passive"))
      (node (ref "EPD_C2") (pin "1") (pinfunction "1_1") (pintype "passive"))
      (node (ref "EPD_C5") (pin "1") (pinfunction "1_1") (pintype "passive"))
      (node (ref "EPD_C6") (pin "1") (pinfunction "1_1") (pintype "passive"))
      (node (ref "EPD_C7") (pin "1") (pinfunction "1_1") (pintype "passive"))
      (node (ref "EPD_C7") (pin "2") (pinfunction "2_2") (pintype "passive"))
      (node (ref "EPD_C8") (pin "1") (pinfunction "1_1") (pintype "passive"))
      (node (ref "EPD_C9") (pin "1") (pinfunction "1_1") (pintype "passive"))
      (node (ref "IC1") (pin "D2") (pinfunction "GND_D2") (pintype "bidirectional"))
      (node (ref "IC2") (pin "B1") (pinfunction "IN/TRIG_B1") (pintype "bidirectional"))
      (node (ref "IC2") (pin "B3") (pinfunction "GND_B3") (pintype "bidirectional"))
      (node (ref "IC3") (pin "8") (pinfunction "GNDIO_8") (pintype "bidirectional"))
      (node (ref "IC3") (pin "9") (pinfunction "GND_9") (pintype "bidirectional"))
      (node (ref "IC9") (pin "B1") (pinfunction "VSEL_B1") (pintype "bidirectional"))
      (node (ref "IC9") (pin "C1") (pinfunction "AGND_C1") (pintype "bidirectional"))
      (node (ref "IC9") (pin "C2") (pinfunction "PGND_1_C2") (pintype "bidirectional"))
      (node (ref "IC9") (pin "C3") (pinfunction "PGND_2_C3") (pintype "bidirectional"))
      (node (ref "J1") (pin "17") (pinfunction "17_17") (pintype "bidirectional"))
      (node (ref "J1") (pin "19") (pinfunction "19_19") (pintype "bidirectional"))
      (node (ref "J1") (pin "8") (pinfunction "8_8") (pintype "bidirectional"))
      (node (ref "J1") (pin "MP1") (pinfunction "MP1_MP1") (pintype "bidirectional"))
      (node (ref "J1") (pin "MP2") (pinfunction "MP2_MP2") (pintype "bidirectional"))
      (node (ref "J2") (pin "3") (pinfunction "3_3") (pintype "bidirectional"))
      (node (ref "J2") (pin "5") (pinfunction "5_5") (pintype "bidirectional"))
      (node (ref "J4") (pin "A12_B1") (pinfunction "GND_A12_B1") (pintype "power_in"))
      (node (ref "J4") (pin "A1_B12") (pinfunction "GND_A1_B12") (pintype "power_in"))
      (node (ref "J4") (pin "SH1") (pinfunction "SHIELD_SH1") (pintype "passive"))
      (node (ref "J4") (pin "SH2") (pinfunction "SHIELD_SH2") (pintype "passive"))
      (node (ref "J4") (pin "SH3") (pinfunction "SHIELD_SH3") (pintype "passive"))
      (node (ref "J4") (pin "SH4") (pinfunction "SHIELD_SH4") (pintype "passive"))
      (node (ref "R1_USB") (pin "1") (pinfunction "1_1") (pintype "bidirectional"))
      (node (ref "R2_EP_DR") (pin "1") (pinfunction "1_1") (pintype "bidirectional"))
      (node (ref "R2_USB") (pin "2") (pinfunction "2_2") (pintype "bidirectional"))
      (node (ref "R3") (pin "1") (pinfunction "1_1") (pintype "bidirectional"))
      (node (ref "R9") (pin "1") (pinfunction "1_1") (pintype "bidirectional"))
      (node (ref "R_TYPE_SEL") (pin "1") (pinfunction "1_1") (pintype "bidirectional"))
      (node (ref "SJ1") (pin "1") (pinfunction "1_1") (pintype "passive"))
      (node (ref "SW_DN") (pin "1") (pinfunction "1_1") (pintype "passive"))
      (node (ref "SW_ENT") (pin "1") (pinfunction "1_1") (pintype "passive"))
      (node (ref "SW_UP") (pin "1") (pinfunction "1_1") (pintype "passive"))
      (node (ref "TP_BAT_GND") (pin "TP") (pinfunction "TP_TP") (pintype "input"))
      (node (ref "TP_GND") (pin "TP") (pinfunction "TP_TP") (pintype "input"))
      (node (ref "U1") (pin "P$74") (pinfunction "VSS_PAD_P$74") (pintype "bidirectional"))
      (node (ref "U1") (pin "P$75") (pinfunction "VSS_PAD_P$75") (pintype "bidirectional"))
      (node (ref "U1") (pin "P$76") (pinfunction "VSS_PAD_P$76") (pintype "bidirectional"))
      (node (ref "U1") (pin "P$77") (pinfunction "VSS_PAD_P$77") (pintype "bidirectional"))
      (node (ref "U1") (pin "P$78") (pinfunction "VSS_PAD_P$78") (pintype "bidirectional"))
      (node (ref "U1") (pin "P$79") (pinfunction "VSS_PAD_P$79") (pintype "bidirectional"))
      (node (ref "U1") (pin "P$80") (pinfunction "VSS_PAD_P$80") (pintype "bidirectional"))
      (node (ref "U1") (pin "P$81") (pinfunction "VSS_PAD_P$81") (pintype "bidirectional"))
      (node (ref "U1") (pin "P$82") (pinfunction "VSS_PAD_P$82") (pintype "bidirectional"))
      (node (ref "U1") (pin "P$83") (pinfunction "VSS_PAD_P$83") (pintype "bidirectional"))
      (node (ref "U1") (pin "P$84") (pinfunction "VSS_PAD_P$84") (pintype "bidirectional"))
      (node (ref "U1") (pin "P$85") (pinfunction "VSS_PAD_P$85") (pintype "bidirectional"))
      (node (ref "U1") (pin "P$86") (pinfunction "VSS_PAD_P$86") (pintype "bidirectional"))
      (node (ref "U1") (pin "P$87") (pinfunction "VSS_PAD_P$87") (pintype "bidirectional"))
      (node (ref "U1") (pin "P$88") (pinfunction "VSS_PAD_P$88") (pintype "bidirectional"))
      (node (ref "U1") (pin "P$89") (pinfunction "VSS_PAD_P$89") (pintype "bidirectional"))
      (node (ref "U1") (pin "P$90") (pinfunction "VSS_PAD_P$90") (pintype "bidirectional"))
      (node (ref "U1") (pin "P$B7") (pinfunction "VSS_P$B7") (pintype "power_in"))
      (node (ref "U1") (pin "P$F23") (pinfunction "VSS_PA_P$F23") (pintype "bidirectional"))
      (node (ref "U3") (pin "1") (pinfunction "CTG_1") (pintype "power_in"))
      (node (ref "U3") (pin "4") (pinfunction "GND_4") (pintype "power_in"))
      (node (ref "U3") (pin "6") (pinfunction "QSTRT_6") (pintype "input"))
      (node (ref "U3") (pin "9") (pinfunction "EP_9") (pintype "power_in"))
      (node (ref "X1") (pin "2") (pinfunction "2_2") (pintype "passive"))
      (node (ref "X1") (pin "4") (pinfunction "4_4") (pintype "passive"))
    )
    (net (code "17") (name "HAPTIC_EN") (class "Default")
      (node (ref "IC2") (pin "A1") (pinfunction "EN_A1") (pintype "bidirectional"))
      (node (ref "U1") (pin "P$U1") (pinfunction "P0.12_P$U1") (pintype "bidirectional"))
    )
    (net (code "18") (name "IMU_INT1") (class "Default")
      (node (ref "IC3") (pin "5") (pinfunction "INT1_5") (pintype "bidirectional"))
      (node (ref "U1") (pin "P$N1") (pinfunction "P0.08_P$N1") (pintype "bidirectional"))
    )
    (net (code "19") (name "IMU_INT2") (class "Default")
      (node (ref "IC3") (pin "6") (pinfunction "INT2_6") (pintype "bidirectional"))
      (node (ref "U1") (pin "P$P2") (pinfunction "P1.08_P$P2") (pintype "bidirectional"))
    )
    (net (code "20") (name "LX1") (class "Default")
      (node (ref "IC9") (pin "B2") (pinfunction "SW1_1_B2") (pintype "bidirectional"))
      (node (ref "IC9") (pin "B3") (pinfunction "SW1_2_B3") (pintype "bidirectional"))
      (node (ref "L7") (pin "1") (pinfunction "1_1") (pintype "bidirectional"))
    )
    (net (code "21") (name "LX2") (class "Default")
      (node (ref "IC9") (pin "D2") (pinfunction "SW2_1_D2") (pintype "bidirectional"))
      (node (ref "IC9") (pin "D3") (pinfunction "SW2_2_D3") (pintype "bidirectional"))
      (node (ref "L7") (pin "2") (pinfunction "2_2") (pintype "bidirectional"))
    )
    (net (code "22") (name "MOSI") (class "Default")
      (node (ref "J1") (pin "14") (pinfunction "14_14") (pintype "bidirectional"))
      (node (ref "U1") (pin "P$B13") (pinfunction "P0.03/AIN1_P$B13") (pintype "bidirectional"))
    )
    (net (code "23") (name "Net-(C17-Pad1)") (class "Default")
      (node (ref "C17") (pin "1") (pinfunction "1_1") (pintype "passive"))
      (node (ref "C18") (pin "1") (pinfunction "1_1") (pintype "passive"))
    )
    (net (code "24") (name "Net-(D2-K)") (class "Default")
      (node (ref "C2-EP-DR") (pin "2") (pinfunction "2_2") (pintype "passive"))
      (node (ref "D2") (pin "1") (pinfunction "K_1") (pintype "bidirectional"))
      (node (ref "D4") (pin "2") (pinfunction "A_2") (pintype "bidirectional"))
    )
    (net (code "25") (name "Net-(D5-A)") (class "Default")
      (node (ref "C2-EP-DR") (pin "1") (pinfunction "1_1") (pintype "passive"))
      (node (ref "D5") (pin "2") (pinfunction "A_2") (pintype "bidirectional"))
      (node (ref "L5") (pin "1") (pinfunction "1_1") (pintype "passive"))
      (node (ref "Q3") (pin "3") (pinfunction "D_3") (pintype "bidirectional"))
    )
    (net (code "26") (name "Net-(EPD_C1-Pad2)") (class "Default")
      (node (ref "EPD_C1") (pin "2") (pinfunction "2_2") (pintype "passive"))
      (node (ref "J1") (pin "5") (pinfunction "5_5") (pintype "bidirectional"))
    )
    (net (code "27") (name "Net-(EPD_C2-Pad2)") (class "Default")
      (node (ref "EPD_C2") (pin "2") (pinfunction "2_2") (pintype "passive"))
      (node (ref "J1") (pin "4") (pinfunction "4_4") (pintype "bidirectional"))
    )
    (net (code "28") (name "Net-(EPD_C6-Pad2)") (class "Default")
      (node (ref "EPD_C6") (pin "2") (pinfunction "2_2") (pintype "passive"))
      (node (ref "J1") (pin "18") (pinfunction "18_18") (pintype "bidirectional"))
    )
    (net (code "29") (name "Net-(EPD_C8-Pad2)") (class "Default")
      (node (ref "EPD_C8") (pin "2") (pinfunction "2_2") (pintype "passive"))
      (node (ref "J1") (pin "20") (pinfunction "20_20") (pintype "bidirectional"))
    )
    (net (code "30") (name "Net-(EPD_C10-Pad2)") (class "Default")
      (node (ref "EPD_C10") (pin "2") (pinfunction "2_2") (pintype "passive"))
      (node (ref "J1") (pin "22") (pinfunction "22_22") (pintype "bidirectional"))
    )
    (net (code "31") (name "Net-(EPD_C12-Pad2)") (class "Default")
      (node (ref "EPD_C12") (pin "2") (pinfunction "2_2") (pintype "passive"))
      (node (ref "J1") (pin "24") (pinfunction "24_24") (pintype "bidirectional"))
    )
    (net (code "32") (name "Net-(IC1-TS{slash}MR)") (class "Default")
      (node (ref "IC1") (pin "D1") (pinfunction "TS/MR_D1") (pintype "bidirectional"))
      (node (ref "R9") (pin "2") (pinfunction "2_2") (pintype "bidirectional"))
    )
    (net (code "33") (name "Net-(IC2-REG)") (class "Default")
      (node (ref "C32") (pin "2") (pinfunction "2_2") (pintype "passive"))
      (node (ref "IC2") (pin "A2") (pinfunction "REG_A2") (pintype "bidirectional"))
    )
    (net (code "34") (name "Net-(IC3-SDO)") (class "Default")
      (node (ref "IC3") (pin "1") (pinfunction "SDO_1") (pintype "bidirectional"))
      (node (ref "R3") (pin "2") (pinfunction "2_2") (pintype "bidirectional"))
    )
    (net (code "35") (name "Net-(IC9-SCL)") (class "Default")
      (node (ref "IC9") (pin "D1") (pinfunction "SCL_D1") (pintype "bidirectional"))
      (node (ref "R4") (pin "2") (pinfunction "2_2") (pintype "bidirectional"))
    )
    (net (code "36") (name "Net-(IC9-SDA)") (class "Default")
      (node (ref "IC9") (pin "E1") (pinfunction "SDA_E1") (pintype "bidirectional"))
      (node (ref "R2") (pin "2") (pinfunction "2_2") (pintype "bidirectional"))
    )
    (net (code "37") (name "Net-(J4-CC1)") (class "Default")
      (node (ref "J4") (pin "A5") (pinfunction "CC1_A5") (pintype "bidirectional"))
      (node (ref "R1_USB") (pin "2") (pinfunction "2_2") (pintype "bidirectional"))
    )
    (net (code "38") (name "Net-(J4-CC2)") (class "Default")
      (node (ref "J4") (pin "B5") (pinfunction "CC2_B5") (pintype "bidirectional"))
      (node (ref "R2_USB") (pin "1") (pinfunction "1_1") (pintype "bidirectional"))
    )
    (net (code "39") (name "Net-(L2-Pad1)") (class "Default")
      (node (ref "L2") (pin "1") (pinfunction "1_1") (pintype "passive"))
      (node (ref "L3") (pin "2") (pinfunction "2_2") (pintype "passive"))
    )
    (net (code "40") (name "Net-(R1_EP_DR-Pad1)") (class "Default")
      (node (ref "R1_EP_DR") (pin "1") (pinfunction "1_1") (pintype "bidirectional"))
      (node (ref "R_TYPE_SEL") (pin "2") (pinfunction "2_2") (pintype "bidirectional"))
      (node (ref "SJ1") (pin "2") (pinfunction "2_2") (pintype "passive"))
    )
    (net (code "41") (name "Net-(U1-ANT)") (class "Default")
      (node (ref "C3") (pin "1") (pinfunction "1_1") (pintype "passive"))
      (node (ref "L1") (pin "2") (pinfunction "2_2") (pintype "passive"))
      (node (ref "U1") (pin "P$H23") (pinfunction "ANT_P$H23") (pintype "bidirectional"))
    )
    (net (code "42") (name "Net-(U1-DCC)") (class "Default")
      (node (ref "L2") (pin "2") (pinfunction "2_2") (pintype "passive"))
      (node (ref "U1") (pin "P$B3") (pinfunction "DCC_P$B3") (pintype "output"))
    )
    (net (code "43") (name "Net-(U1-DEC2)") (class "Default")
      (node (ref "C13") (pin "1") (pinfunction "1_1") (pintype "passive"))
      (node (ref "U1") (pin "P$A18") (pinfunction "DEC2_P$A18") (pintype "bidirectional"))
    )
    (net (code "44") (name "Net-(U1-DEC3V3)") (class "Default")
      (node (ref "C20") (pin "1") (pinfunction "1_1") (pintype "passive"))
      (node (ref "U1") (pin "P$AC5") (pinfunction "DEC3V3_P$AC5") (pintype "bidirectional"))
    )
    (net (code "45") (name "Net-(U1-DEC5)") (class "Default")
      (node (ref "C9") (pin "1") (pinfunction "1_1") (pintype "passive"))
      (node (ref "U1") (pin "P$N24") (pinfunction "DEC5_P$N24") (pintype "bidirectional"))
    )
    (net (code "46") (name "Net-(U1-XC1)") (class "Default")
      (node (ref "C2") (pin "1") (pinfunction "1_1") (pintype "passive"))
      (node (ref "U1") (pin "P$B24") (pinfunction "XC1_P$B24") (pintype "input"))
      (node (ref "X1") (pin "1") (pinfunction "1_1") (pintype "passive"))
    )
    (net (code "47") (name "Net-(U1-XC2)") (class "Default")
      (node (ref "C1") (pin "1") (pinfunction "1_1") (pintype "passive"))
      (node (ref "U1") (pin "P$A23") (pinfunction "XC2_P$A23") (pintype "output"))
      (node (ref "X1") (pin "3") (pinfunction "3_3") (pintype "passive"))
    )
    (net (code "48") (name "OUT+") (class "Default")
      (node (ref "IC2") (pin "A3") (pinfunction "OUT+_A3") (pintype "bidirectional"))
      (node (ref "TP_OP1") (pin "TP") (pinfunction "TP_TP") (pintype "input"))
    )
    (net (code "49") (name "OUT-") (class "Default")
      (node (ref "IC2") (pin "C3") (pinfunction "OUT-_C3") (pintype "bidirectional"))
      (node (ref "TP_ON") (pin "TP") (pinfunction "TP_TP") (pintype "input"))
    )
    (net (code "50") (name "P0.00{slash}XL1") (class "Default")
      (node (ref "C18") (pin "2") (pinfunction "2_2") (pintype "passive"))
      (node (ref "U1") (pin "P$D2") (pinfunction "P0.00/XL1_P$D2") (pintype "bidirectional"))
      (node (ref "X2") (pin "2") (pinfunction "2_2") (pintype "passive"))
    )
    (net (code "51") (name "P0.00{slash}XL2") (class "Default")
      (node (ref "C17") (pin "2") (pinfunction "2_2") (pintype "passive"))
      (node (ref "U1") (pin "P$F2") (pinfunction "P0.01/XL2_P$F2") (pintype "bidirectional"))
      (node (ref "X2") (pin "1") (pinfunction "1_1") (pintype "passive"))
    )
    (net (code "52") (name "P0.04") (class "Default")
      (node (ref "U1") (pin "P$J1") (pinfunction "P0.04/AIN2_P$J1") (pintype "bidirectional"))
    )
    (net (code "53") (name "P0.09") (class "Default")
      (node (ref "U1") (pin "P$L24") (pinfunction "P0.09/NFC1_P$L24") (pintype "bidirectional"))
    )
    (net (code "54") (name "P0.13") (class "Default")
      (node (ref "C30") (pin "2") (pinfunction "2_2") (pintype "passive"))
      (node (ref "R5") (pin "1") (pinfunction "1_1") (pintype "bidirectional"))
      (node (ref "SW_UP") (pin "2") (pinfunction "2_2") (pintype "passive"))
      (node (ref "U1") (pin "P$AD8") (pinfunction "P0.13_P$AD8") (pintype "bidirectional"))
    )
    (net (code "55") (name "P0.14") (class "Default")
      (node (ref "C31") (pin "2") (pinfunction "2_2") (pintype "passive"))
      (node (ref "R8") (pin "1") (pinfunction "1_1") (pintype "bidirectional"))
      (node (ref "SW_ENT") (pin "2") (pinfunction "2_2") (pintype "passive"))
      (node (ref "U1") (pin "P$AC9") (pinfunction "P0.14_P$AC9") (pintype "bidirectional"))
    )
    (net (code "56") (name "P0.19") (class "Default")
      (node (ref "U1") (pin "P$AC15") (pinfunction "P0.19_P$AC15") (pintype "bidirectional"))
    )
    (net (code "57") (name "P0.20") (class "Default")
      (node (ref "U1") (pin "P$AD16") (pinfunction "P0.20_P$AD16") (pintype "bidirectional"))
    )
    (net (code "58") (name "P0.22") (class "Default")
      (node (ref "U1") (pin "P$AC17") (pinfunction "P0.21_P$AC17") (pintype "bidirectional"))
    )
    (net (code "59") (name "P0.23") (class "Default")
      (node (ref "U1") (pin "P$AC19") (pinfunction "P0.23_P$AC19") (pintype "bidirectional"))
    )
    (net (code "60") (name "P0.24") (class "Default")
      (node (ref "U1") (pin "P$AD20") (pinfunction "P0.24_P$AD20") (pintype "bidirectional"))
    )
    (net (code "61") (name "P0.25") (class "Default")
      (node (ref "U1") (pin "P$AC21") (pinfunction "P0.25_P$AC21") (pintype "bidirectional"))
    )
    (net (code "62") (name "P0.26") (class "Default")
      (node (ref "U1") (pin "P$G1") (pinfunction "P0.26_P$G1") (pintype "bidirectional"))
    )
    (net (code "63") (name "P0.27") (class "Default")
      (node (ref "U1") (pin "P$H2") (pinfunction "P0.27_P$H2") (pintype "bidirectional"))
    )
    (net (code "64") (name "P0.28") (class "Default")
      (node (ref "U1") (pin "P$B11") (pinfunction "P0.28/AIN4_P$B11") (pintype "bidirectional"))
    )
    (net (code "65") (name "P0.29") (class "Default")
      (node (ref "U1") (pin "P$A10") (pinfunction "P0.29/AIN5_P$A10") (pintype "bidirectional"))
    )
    (net (code "66") (name "P0.30") (class "Default")
      (node (ref "U1") (pin "P$B9") (pinfunction "P0.30/AIN6_P$B9") (pintype "bidirectional"))
    )
    (net (code "67") (name "P0.31") (class "Default")
      (node (ref "U1") (pin "P$A8") (pinfunction "P0.31/AIN7_P$A8") (pintype "bidirectional"))
    )
    (net (code "68") (name "P1.01") (class "Default")
      (node (ref "Q1") (pin "1") (pinfunction "G_1") (pintype "bidirectional"))
      (node (ref "R_PWR_EPD") (pin "1") (pinfunction "1_1") (pintype "bidirectional"))
      (node (ref "U1") (pin "P$Y23") (pinfunction "P1.01_P$Y23") (pintype "bidirectional"))
    )
    (net (code "69") (name "P1.02") (class "Default")
      (node (ref "C29") (pin "2") (pinfunction "2_2") (pintype "passive"))
      (node (ref "R7") (pin "1") (pinfunction "1_1") (pintype "bidirectional"))
      (node (ref "SW_DN") (pin "2") (pinfunction "2_2") (pintype "passive"))
      (node (ref "U1") (pin "P$W24") (pinfunction "P1.02_P$W24") (pintype "bidirectional"))
    )
    (net (code "70") (name "P1.03") (class "Default")
      (node (ref "U1") (pin "P$V23") (pinfunction "P1.03_P$V23") (pintype "bidirectional"))
    )
    (net (code "71") (name "P1.04") (class "Default")
      (node (ref "U1") (pin "P$U24") (pinfunction "P1.04_P$U24") (pintype "bidirectional"))
    )
    (net (code "72") (name "P1.05") (class "Default")
      (node (ref "U1") (pin "P$T23") (pinfunction "P1.05_P$T23") (pintype "bidirectional"))
    )
    (net (code "73") (name "P1.06") (class "Default")
      (node (ref "U1") (pin "P$R24") (pinfunction "P1.06_P$R24") (pintype "bidirectional"))
    )
    (net (code "74") (name "P1.07") (class "Default")
      (node (ref "U1") (pin "P$P23") (pinfunction "P1.07_P$P23") (pintype "bidirectional"))
    )
    (net (code "75") (name "P1.09") (class "Default")
      (node (ref "U1") (pin "P$R1") (pinfunction "P1.09_P$R1") (pintype "bidirectional"))
    )
    (net (code "76") (name "P1.10") (class "Default")
      (node (ref "U1") (pin "P$A20") (pinfunction "P1.10_P$A20") (pintype "bidirectional"))
    )
    (net (code "77") (name "P1.11") (class "Default")
      (node (ref "U1") (pin "P$B19") (pinfunction "P1.11_P$B19") (pintype "bidirectional"))
    )
    (net (code "78") (name "P1.12") (class "Default")
      (node (ref "U1") (pin "P$B17") (pinfunction "P1.12_P$B17") (pintype "bidirectional"))
    )
    (net (code "79") (name "P1.13") (class "Default")
      (node (ref "U1") (pin "P$A16") (pinfunction "P1.13_P$A16") (pintype "bidirectional"))
    )
    (net (code "80") (name "P1.14") (class "Default")
      (node (ref "U1") (pin "P$B15") (pinfunction "P1.14_P$B15") (pintype "bidirectional"))
    )
    (net (code "81") (name "P1.15") (class "Default")
      (node (ref "U1") (pin "P$A14") (pinfunction "P1.15_P$A14") (pintype "bidirectional"))
    )
    (net (code "82") (name "PMIC_INT") (class "Default")
      (node (ref "IC1") (pin "A1") (pinfunction "~{INT}_A1") (pintype "bidirectional"))
      (node (ref "U1") (pin "P$T2") (pinfunction "P0.11_P$T2") (pintype "bidirectional"))
    )
    (net (code "83") (name "PREVGH") (class "Default")
      (node (ref "D5") (pin "1") (pinfunction "K_1") (pintype "bidirectional"))
      (node (ref "EPD_C9") (pin "2") (pinfunction "2_2") (pintype "passive"))
      (node (ref "J1") (pin "21") (pinfunction "21_21") (pintype "bidirectional"))
    )
    (net (code "84") (name "PREVGL") (class "Default")
      (node (ref "D2") (pin "2") (pinfunction "A_2") (pintype "bidirectional"))
      (node (ref "EPD_C11") (pin "2") (pinfunction "2_2") (pintype "passive"))
      (node (ref "J1") (pin "23") (pinfunction "23_23") (pintype "bidirectional"))
    )
    (net (code "85") (name "RESE") (class "Default")
      (node (ref "J1") (pin "3") (pinfunction "3_3") (pintype "bidirectional"))
      (node (ref "Q3") (pin "2") (pinfunction "S_2") (pintype "bidirectional"))
      (node (ref "R1_EP_DR") (pin "2") (pinfunction "2_2") (pintype "bidirectional"))
    )
    (net (code "86") (name "RESET") (class "Default")
      (node (ref "J2") (pin "6") (pinfunction "6_6") (pintype "bidirectional"))
      (node (ref "TP_RESET") (pin "TP") (pinfunction "TP_TP") (pintype "input"))
      (node (ref "U1") (pin "P$AC13") (pinfunction "P0.18/RESET_P$AC13") (pintype "bidirectional"))
    )
    (net (code "87") (name "RF") (class "Default")
      (node (ref "ANT1") (pin "1") (pinfunction "FEED_1") (pintype "input"))
      (node (ref "C22") (pin "1") (pinfunction "1_1") (pintype "passive"))
      (node (ref "C4") (pin "1") (pinfunction "1_1") (pintype "passive"))
      (node (ref "L1") (pin "1") (pinfunction "1_1") (pintype "passive"))
    )
    (net (code "88") (name "SCK") (class "Default")
      (node (ref "J1") (pin "13") (pinfunction "13_13") (pintype "bidirectional"))
      (node (ref "U1") (pin "P$A12") (pinfunction "P0.02/AIN0_P$A12") (pintype "bidirectional"))
    )
    (net (code "89") (name "SCL") (class "Default")
      (node (ref "IC1") (pin "B1") (pinfunction "SCL_B1") (pintype "bidirectional"))
      (node (ref "IC2") (pin "C1") (pinfunction "SCL_C1") (pintype "bidirectional"))
      (node (ref "IC3") (pin "12") (pinfunction "SCX_12") (pintype "bidirectional"))
      (node (ref "R17") (pin "2") (pinfunction "2_2") (pintype "bidirectional"))
      (node (ref "R4") (pin "1") (pinfunction "1_1") (pintype "bidirectional"))
      (node (ref "TP_SCL") (pin "TP") (pinfunction "TP_TP") (pintype "input"))
      (node (ref "U1") (pin "P$M2") (pinfunction "P0.07_P$M2") (pintype "bidirectional"))
      (node (ref "U3") (pin "7") (pinfunction "SCL_7") (pintype "input"))
    )
    (net (code "90") (name "SDA") (class "Default")
      (node (ref "IC1") (pin "C1") (pinfunction "SDA_C1") (pintype "bidirectional"))
      (node (ref "IC2") (pin "B2") (pinfunction "SDA_B2") (pintype "bidirectional"))
      (node (ref "IC3") (pin "2") (pinfunction "SDX_2") (pintype "bidirectional"))
      (node (ref "R18") (pin "2") (pinfunction "2_2") (pintype "bidirectional"))
      (node (ref "R2") (pin "1") (pinfunction "1_1") (pintype "bidirectional"))
      (node (ref "TP_SDA") (pin "TP") (pinfunction "TP_TP") (pintype "input"))
      (node (ref "U1") (pin "P$L1") (pinfunction "P0.06_P$L1") (pintype "bidirectional"))
      (node (ref "U3") (pin "8") (pinfunction "SDA_8") (pintype "bidirectional"))
    )
    (net (code "91") (name "SWDCLK") (class "Default")
      (node (ref "J2") (pin "4") (pinfunction "4_4") (pintype "bidirectional"))
      (node (ref "TP_SWDCLK") (pin "TP") (pinfunction "TP_TP") (pintype "input"))
      (node (ref "U1") (pin "P$AA24") (pinfunction "SWDCLK_P$AA24") (pintype "input"))
    )
    (net (code "92") (name "SWDIO") (class "Default")
      (node (ref "J2") (pin "2") (pinfunction "2_2") (pintype "bidirectional"))
      (node (ref "TP_SWDIO") (pin "TP") (pinfunction "TP_TP") (pintype "input"))
      (node (ref "U1") (pin "P$AC24") (pinfunction "SWDIO_P$AC24") (pintype "bidirectional"))
    )
    (net (code "93") (name "SWO") (class "Default")
      (node (ref "TP_SWO") (pin "TP") (pinfunction "TP_TP") (pintype "input"))
      (node (ref "U1") (pin "P$AD22") (pinfunction "P1.00_P$AD22") (pintype "bidirectional"))
    )
    (net (code "94") (name "VBAT") (class "Default")
      (node (ref "C27") (pin "2") (pinfunction "2_2") (pintype "passive"))
      (node (ref "C37") (pin "2") (pinfunction "2_2") (pintype "passive"))
      (node (ref "IC1") (pin "C2") (pinfunction "BAT_C2") (pintype "bidirectional"))
      (node (ref "TP_VBAT") (pin "TP") (pinfunction "TP_TP") (pintype "input"))
      (node (ref "U3") (pin "2") (pinfunction "CELL_2") (pintype "power_in"))
      (node (ref "U3") (pin "3") (pinfunction "VDD_3") (pintype "power_in"))
    )
    (net (code "95") (name "VBUS") (class "Default")
      (node (ref "C21") (pin "1") (pinfunction "1_1") (pintype "passive"))
      (node (ref "C38") (pin "2") (pinfunction "2_2") (pintype "passive"))
      (node (ref "C42") (pin "1") (pinfunction "1_1") (pintype "passive"))
      (node (ref "C43") (pin "2") (pinfunction "2_2") (pintype "passive"))
      (node (ref "D1") (pin "5") (pinfunction "VBUS_5") (pintype "bidirectional"))
      (node (ref "IC1") (pin "A2") (pinfunction "IN_A2") (pintype "bidirectional"))
      (node (ref "J4") (pin "A4_B9") (pinfunction "VBUS_A4_B9") (pintype "power_in"))
      (node (ref "J4") (pin "A9_B4") (pinfunction "VBUS_A9_B4") (pintype "power_in"))
      (node (ref "U1") (pin "P$AD2") (pinfunction "VBUS_P$AD2") (pintype "power_in"))
    )
    (net (code "96") (name "VREG") (class "Default")
      (node (ref "C23") (pin "1") (pinfunction "1_1") (pintype "passive"))
      (node (ref "C24") (pin "2") (pinfunction "2_2") (pintype "passive"))
      (node (ref "C39") (pin "1") (pinfunction "1_1") (pintype "passive"))
      (node (ref "IC1") (pin "B2") (pinfunction "SYS_B2") (pintype "bidirectional"))
      (node (ref "IC9") (pin "A1") (pinfunction "EN_A1") (pintype "bidirectional"))
      (node (ref "IC9") (pin "A2") (pinfunction "VIN_1_A2") (pintype "bidirectional"))
      (node (ref "IC9") (pin "A3") (pinfunction "VIN_2_A3") (pintype "bidirectional"))
      (node (ref "TP_VREG") (pin "TP") (pinfunction "TP_TP") (pintype "input"))
    )
    (net (code "97") (name "unconnected-(ANT1-NC-Pad2)") (class "Default")
      (node (ref "ANT1") (pin "2") (pinfunction "NC_2") (pintype "no_connect"))
    )
    (net (code "98") (name "unconnected-(IC3-ASCL-Pad11)") (class "Default")
      (node (ref "IC3") (pin "11") (pinfunction "ASCL_11") (pintype "bidirectional"))
    )
    (net (code "99") (name "unconnected-(IC3-ASDA-Pad4)") (class "Default")
      (node (ref "IC3") (pin "4") (pinfunction "ASDA_4") (pintype "bidirectional"))
    )
    (net (code "100") (name "unconnected-(J1-Pad1)") (class "Default")
      (node (ref "J1") (pin "1") (pinfunction "1_1") (pintype "bidirectional"))
    )
    (net (code "101") (name "unconnected-(J1-Pad6)") (class "Default")
      (node (ref "J1") (pin "6") (pinfunction "6_6") (pintype "bidirectional"))
    )
    (net (code "102") (name "unconnected-(J1-Pad7)") (class "Default")
      (node (ref "J1") (pin "7") (pinfunction "7_7") (pintype "bidirectional"))
    )
    (net (code "103") (name "unconnected-(J4-SBU1-PadA8)") (class "Default")
      (node (ref "J4") (pin "A8") (pinfunction "SBU1_A8") (pintype "bidirectional"))
    )
    (net (code "104") (name "unconnected-(J4-SBU2-PadB8)") (class "Default")
      (node (ref "J4") (pin "B8") (pinfunction "SBU2_B8") (pintype "bidirectional"))
    )
    (net (code "105") (name "unconnected-(U1-DCCH-PadP$AB2)") (class "Default")
      (node (ref "U1") (pin "P$AB2") (pinfunction "DCCH_P$AB2") (pintype "bidirectional"))
    )
    (net (code "106") (name "unconnected-(U1-P0.22-PadP$AD18)") (class "Default")
      (node (ref "U1") (pin "P$AD18") (pinfunction "P0.22_P$AD18") (pintype "bidirectional"))
    )
  )
)
